# PCB_SCH_Right_Main.net
KiCad netlist of a schematic drawn in EasyEDA Pro
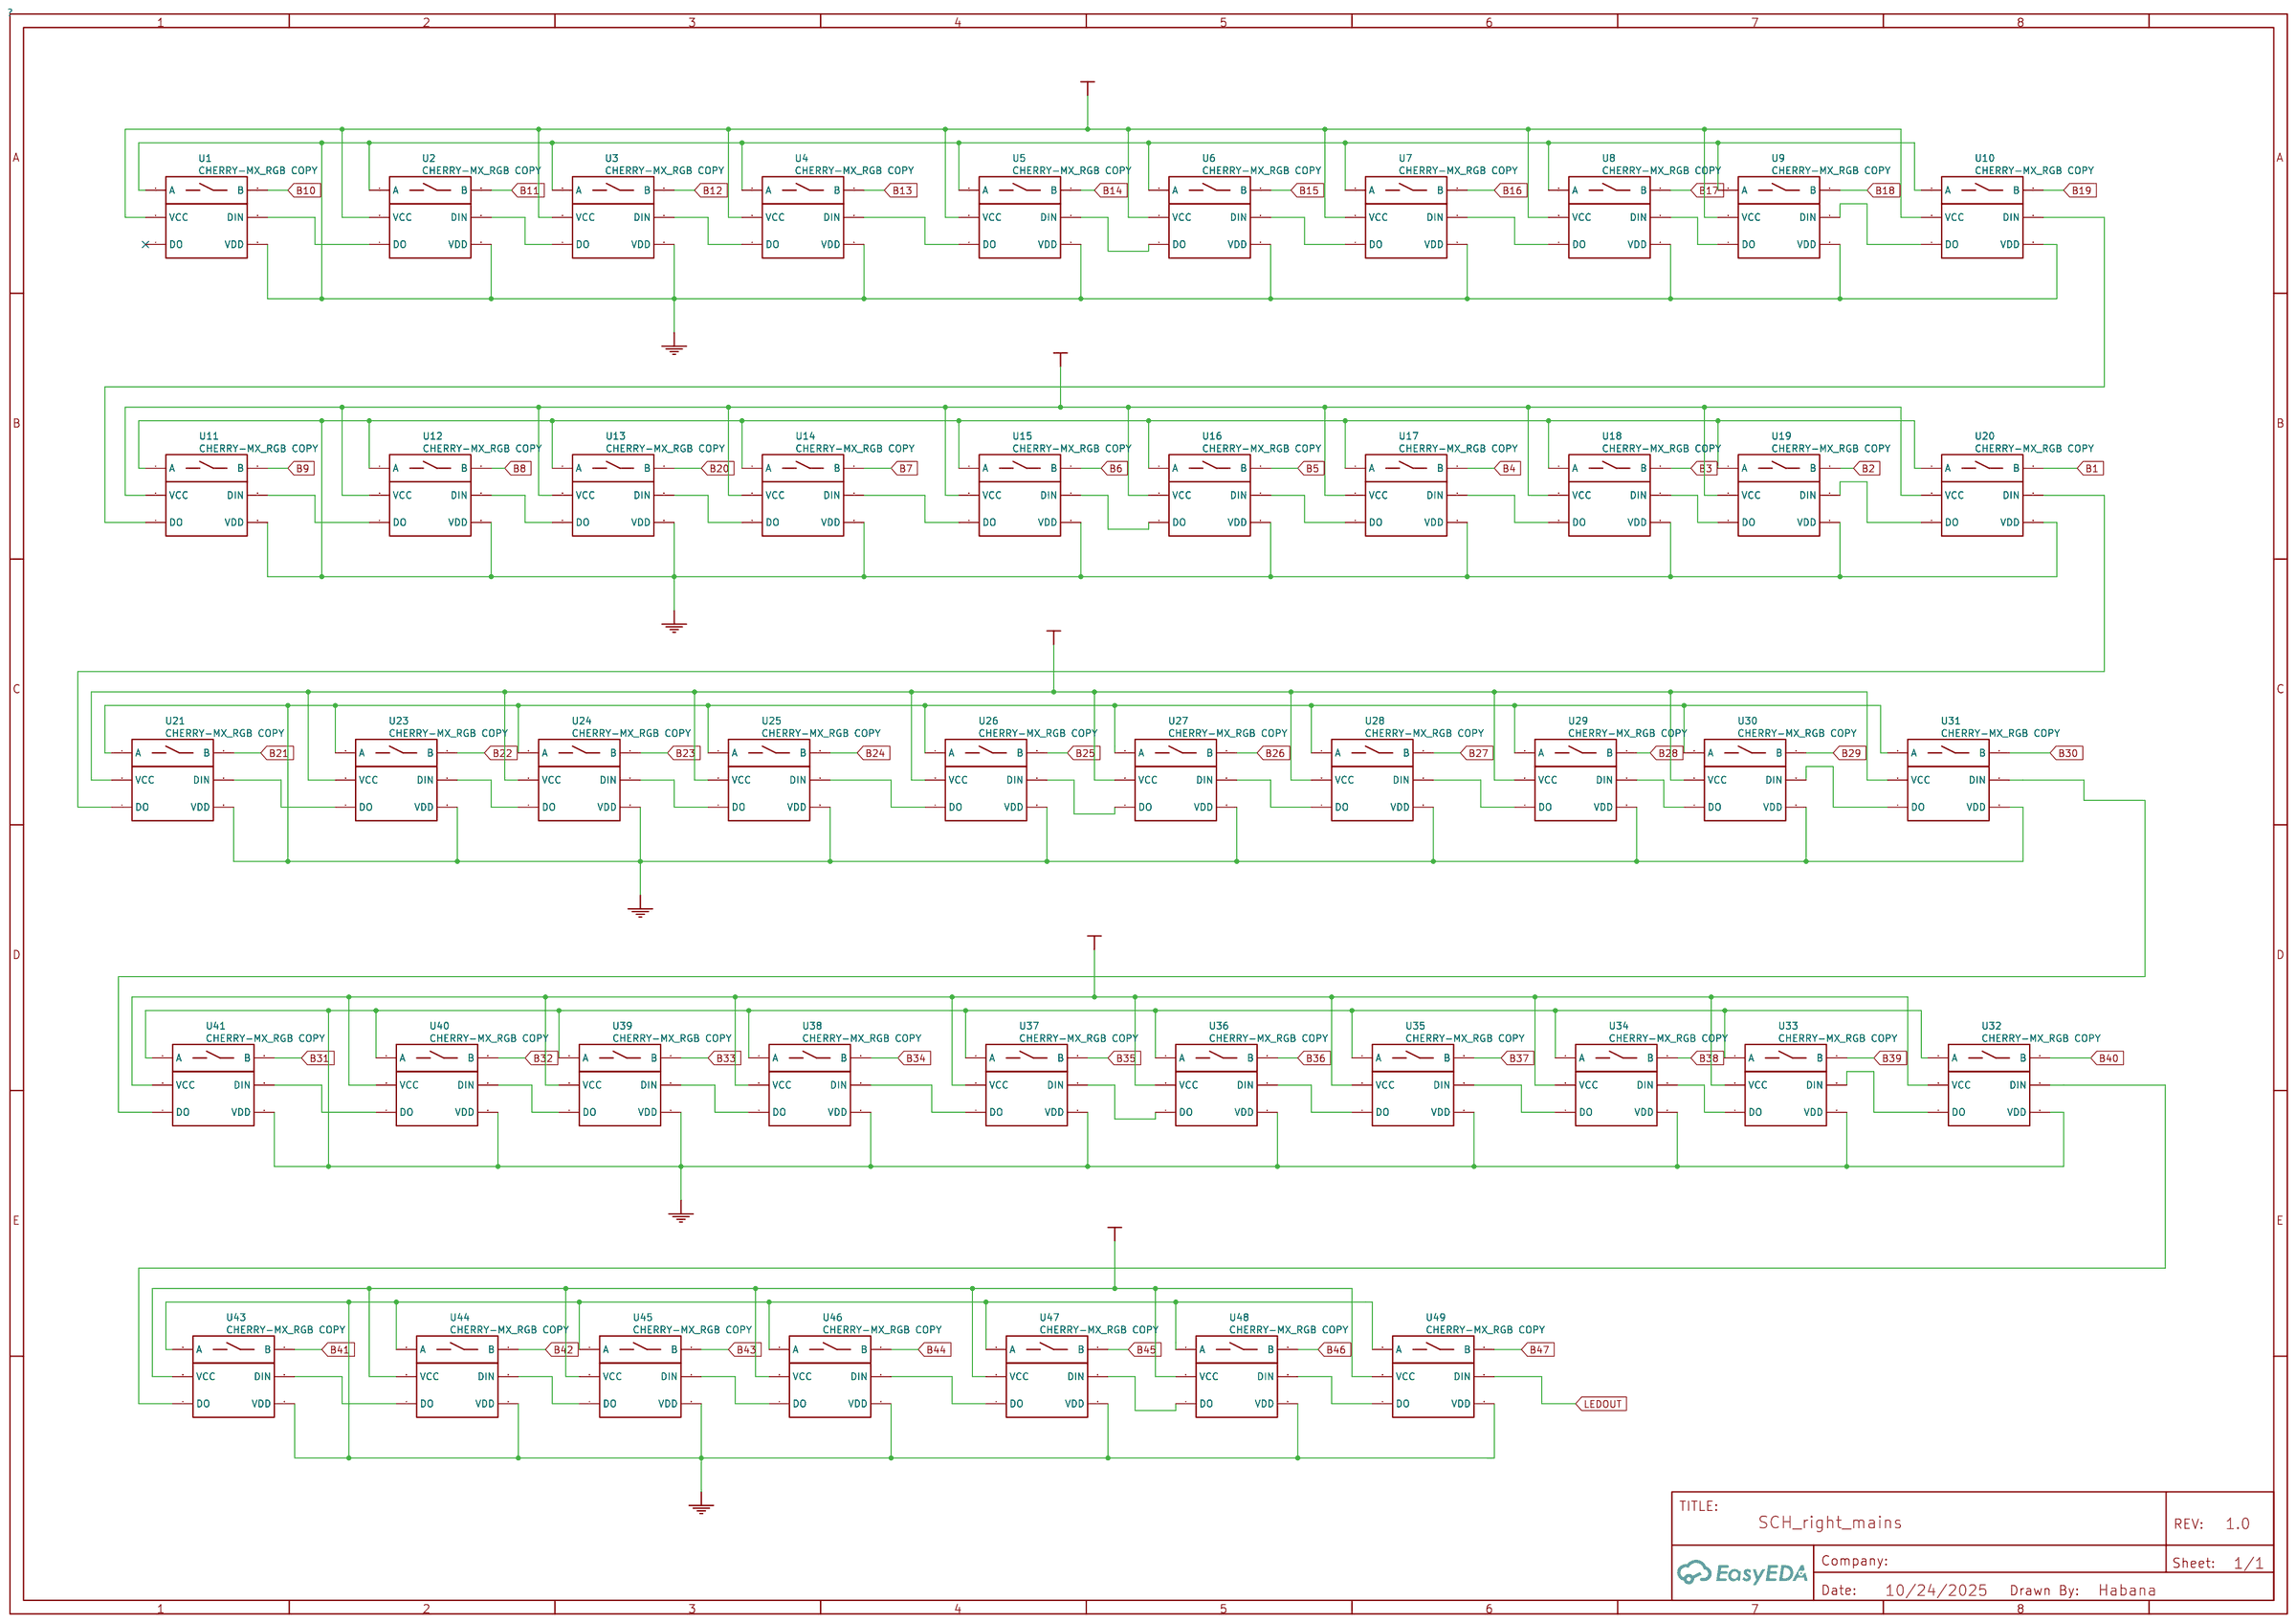
[diagram p0: led and buttons]
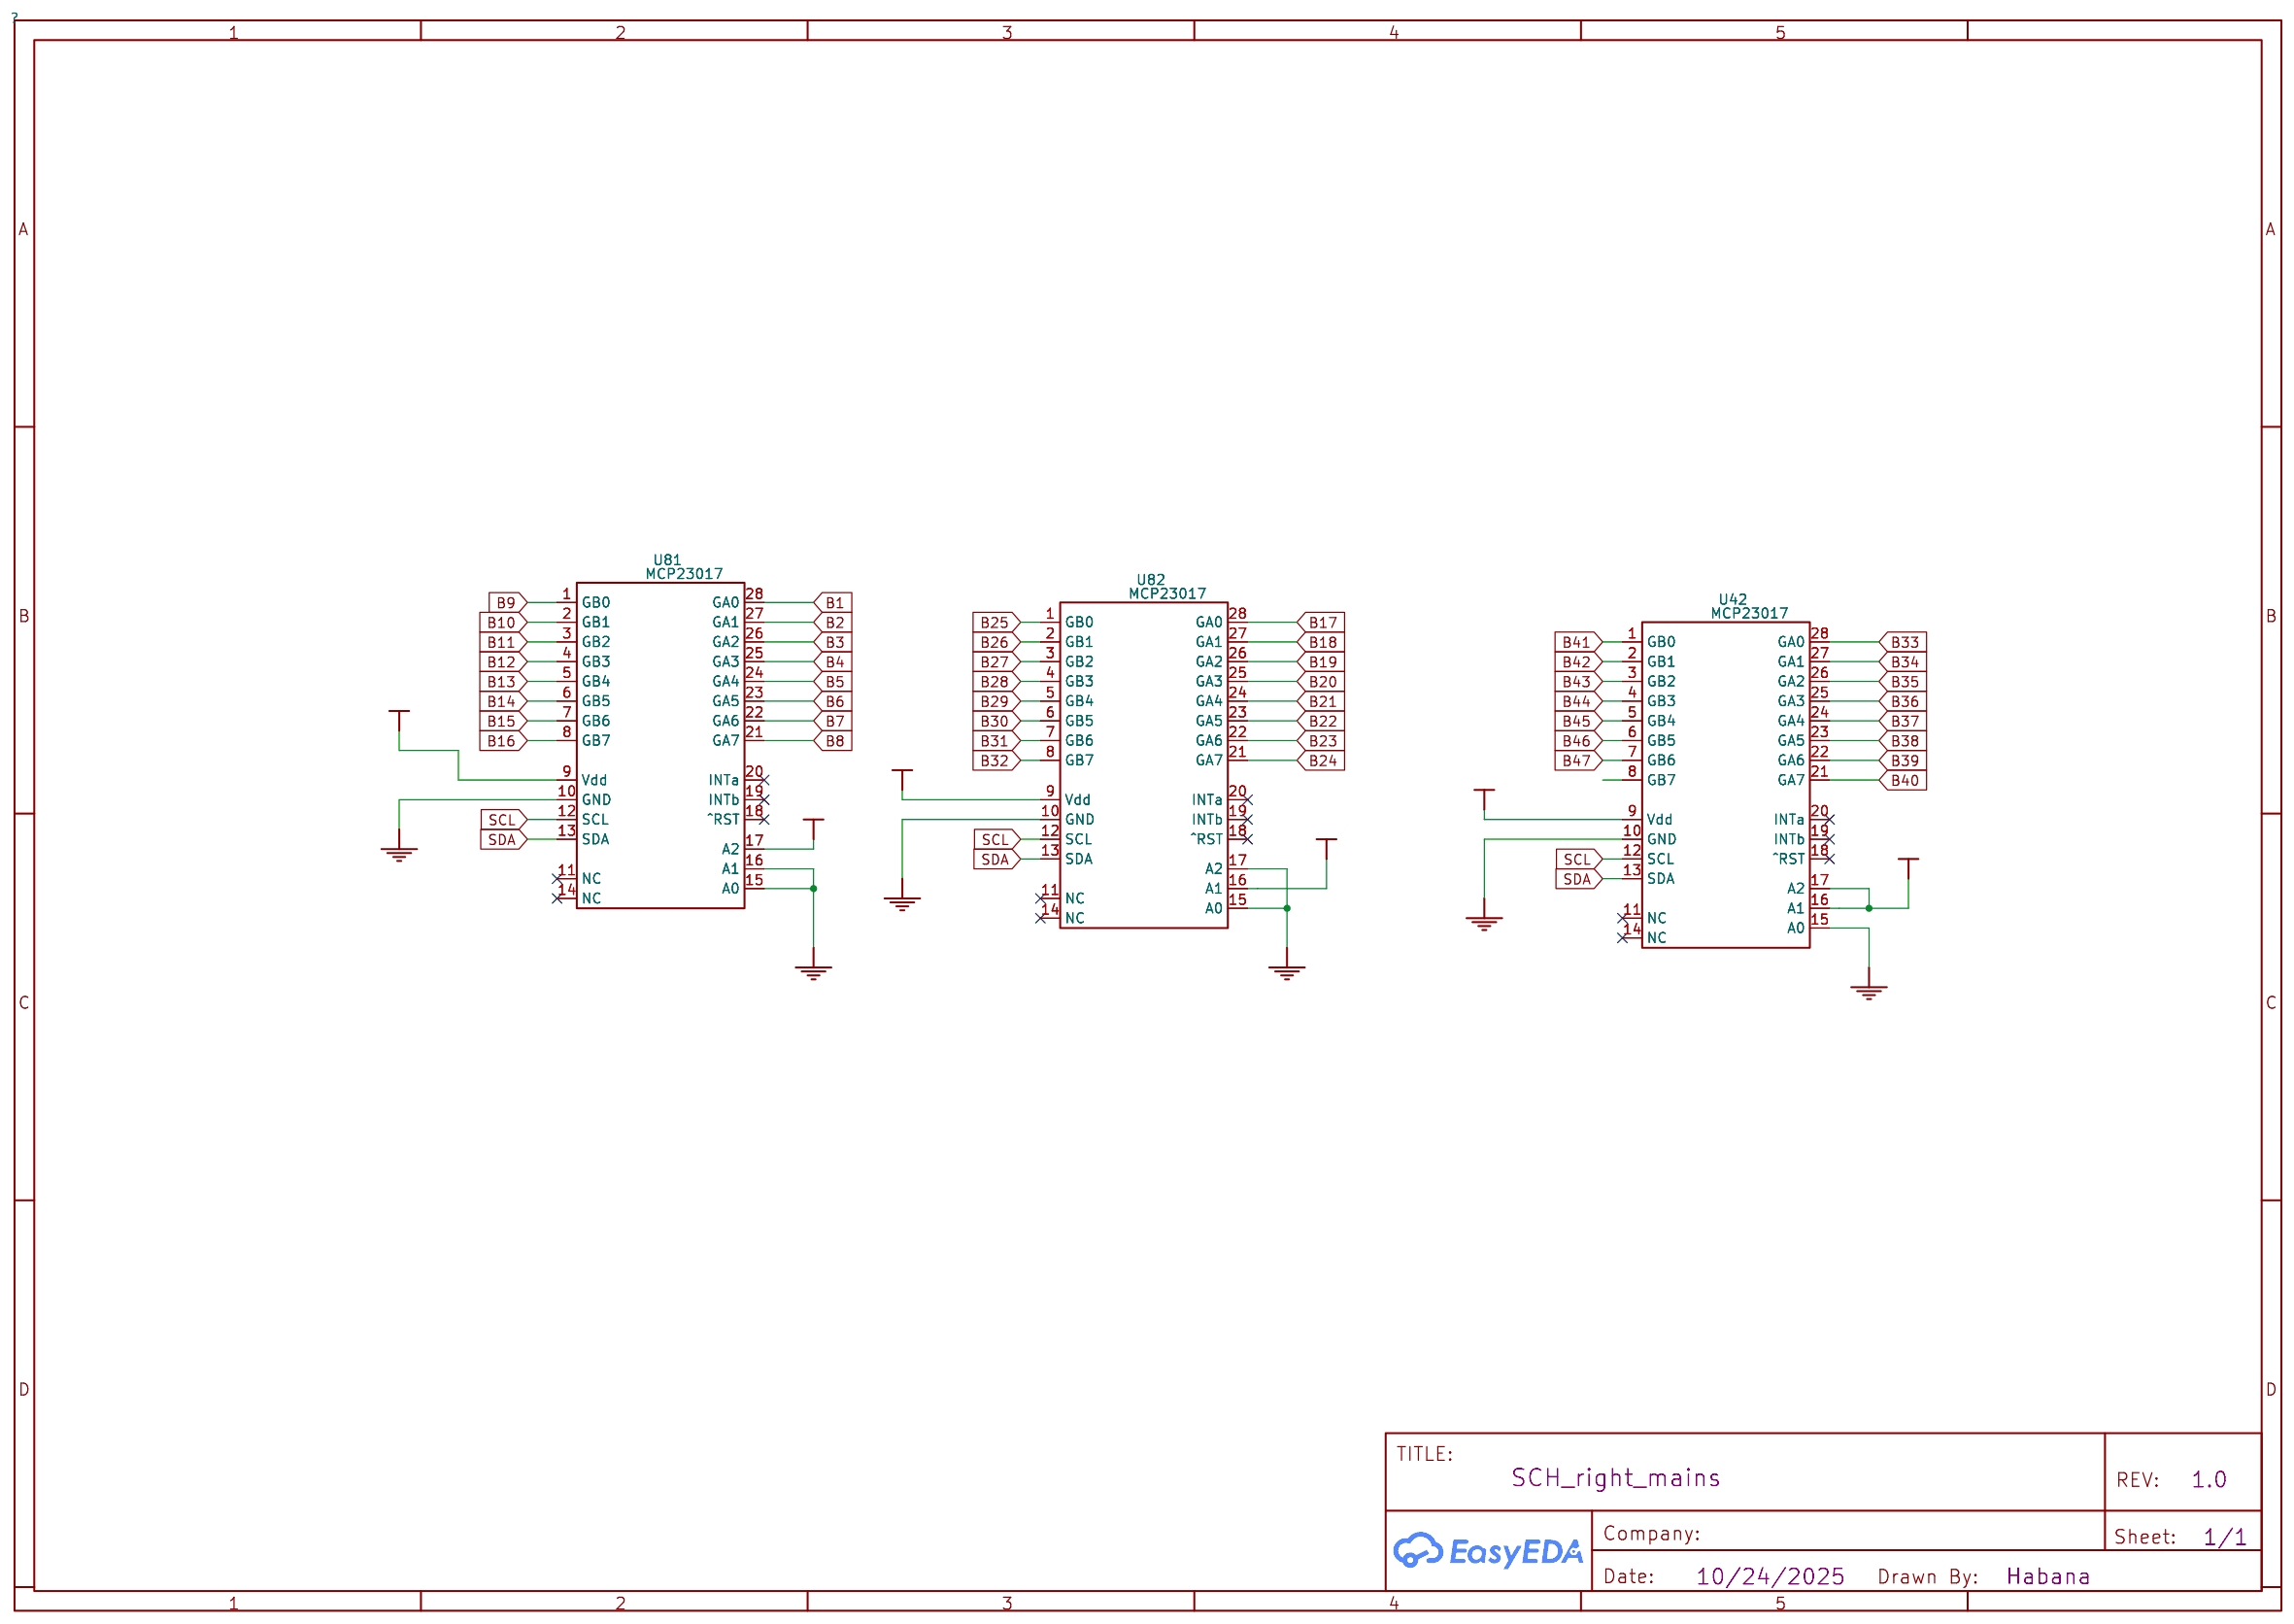
[diagram p1: drivers]
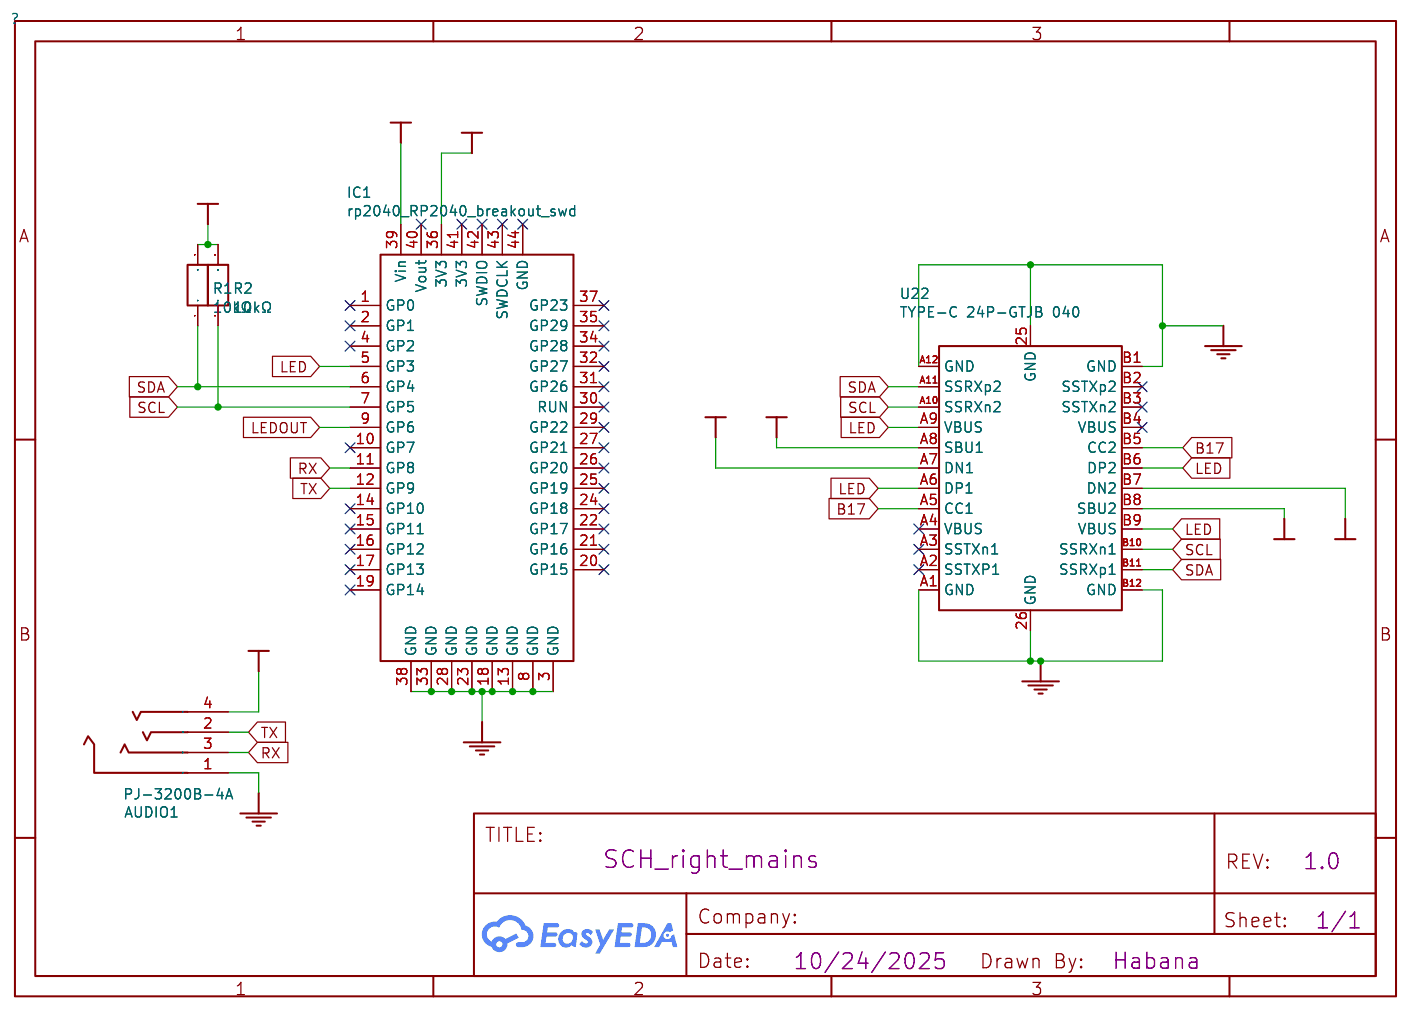
[diagram p2: micro_controller]

(export (version "E")
  (design (tool "Eeschema 10.0.6"))
  (components
    (comp (ref "U1")
      (value "CHERRY-MX_RGB COPY")
      (fields (field (name "Contributor") "unrealin01"))
      (libsource (lib "easyedapro") (part "CHERRY-MX_RGB COPY"))
    )
    (comp (ref "U2")
      (value "CHERRY-MX_RGB COPY")
      (fields (field (name "Contributor") "unrealin01"))
      (libsource (lib "easyedapro") (part "CHERRY-MX_RGB COPY"))
    )
    (comp (ref "U3")
      (value "CHERRY-MX_RGB COPY")
      (fields (field (name "Contributor") "unrealin01"))
      (libsource (lib "easyedapro") (part "CHERRY-MX_RGB COPY"))
    )
    (comp (ref "U4")
      (value "CHERRY-MX_RGB COPY")
      (fields (field (name "Contributor") "unrealin01"))
      (libsource (lib "easyedapro") (part "CHERRY-MX_RGB COPY"))
    )
    (comp (ref "U5")
      (value "CHERRY-MX_RGB COPY")
      (fields (field (name "Contributor") "unrealin01"))
      (libsource (lib "easyedapro") (part "CHERRY-MX_RGB COPY"))
    )
    (comp (ref "U6")
      (value "CHERRY-MX_RGB COPY")
      (fields (field (name "Contributor") "unrealin01"))
      (libsource (lib "easyedapro") (part "CHERRY-MX_RGB COPY"))
    )
    (comp (ref "U7")
      (value "CHERRY-MX_RGB COPY")
      (fields (field (name "Contributor") "unrealin01"))
      (libsource (lib "easyedapro") (part "CHERRY-MX_RGB COPY"))
    )
    (comp (ref "U8")
      (value "CHERRY-MX_RGB COPY")
      (fields (field (name "Contributor") "unrealin01"))
      (libsource (lib "easyedapro") (part "CHERRY-MX_RGB COPY"))
    )
    (comp (ref "U9")
      (value "CHERRY-MX_RGB COPY")
      (fields (field (name "Contributor") "unrealin01"))
      (libsource (lib "easyedapro") (part "CHERRY-MX_RGB COPY"))
    )
    (comp (ref "U10")
      (value "CHERRY-MX_RGB COPY")
      (fields (field (name "Contributor") "unrealin01"))
      (libsource (lib "easyedapro") (part "CHERRY-MX_RGB COPY"))
    )
    (comp (ref "U11")
      (value "CHERRY-MX_RGB COPY")
      (fields (field (name "Contributor") "unrealin01"))
      (libsource (lib "easyedapro") (part "CHERRY-MX_RGB COPY"))
    )
    (comp (ref "U12")
      (value "CHERRY-MX_RGB COPY")
      (fields (field (name "Contributor") "unrealin01"))
      (libsource (lib "easyedapro") (part "CHERRY-MX_RGB COPY"))
    )
    (comp (ref "U13")
      (value "CHERRY-MX_RGB COPY")
      (fields (field (name "Contributor") "unrealin01"))
      (libsource (lib "easyedapro") (part "CHERRY-MX_RGB COPY"))
    )
    (comp (ref "U14")
      (value "CHERRY-MX_RGB COPY")
      (fields (field (name "Contributor") "unrealin01"))
      (libsource (lib "easyedapro") (part "CHERRY-MX_RGB COPY"))
    )
    (comp (ref "U15")
      (value "CHERRY-MX_RGB COPY")
      (fields (field (name "Contributor") "unrealin01"))
      (libsource (lib "easyedapro") (part "CHERRY-MX_RGB COPY"))
    )
    (comp (ref "U16")
      (value "CHERRY-MX_RGB COPY")
      (fields (field (name "Contributor") "unrealin01"))
      (libsource (lib "easyedapro") (part "CHERRY-MX_RGB COPY"))
    )
    (comp (ref "U17")
      (value "CHERRY-MX_RGB COPY")
      (fields (field (name "Contributor") "unrealin01"))
      (libsource (lib "easyedapro") (part "CHERRY-MX_RGB COPY"))
    )
    (comp (ref "U18")
      (value "CHERRY-MX_RGB COPY")
      (fields (field (name "Contributor") "unrealin01"))
      (libsource (lib "easyedapro") (part "CHERRY-MX_RGB COPY"))
    )
    (comp (ref "U19")
      (value "CHERRY-MX_RGB COPY")
      (fields (field (name "Contributor") "unrealin01"))
      (libsource (lib "easyedapro") (part "CHERRY-MX_RGB COPY"))
    )
    (comp (ref "U20")
      (value "CHERRY-MX_RGB COPY")
      (fields (field (name "Contributor") "unrealin01"))
      (libsource (lib "easyedapro") (part "CHERRY-MX_RGB COPY"))
    )
    (comp (ref "U21")
      (value "CHERRY-MX_RGB COPY")
      (fields (field (name "Contributor") "unrealin01"))
      (libsource (lib "easyedapro") (part "CHERRY-MX_RGB COPY"))
    )
    (comp (ref "U23")
      (value "CHERRY-MX_RGB COPY")
      (fields (field (name "Contributor") "unrealin01"))
      (libsource (lib "easyedapro") (part "CHERRY-MX_RGB COPY"))
    )
    (comp (ref "U24")
      (value "CHERRY-MX_RGB COPY")
      (fields (field (name "Contributor") "unrealin01"))
      (libsource (lib "easyedapro") (part "CHERRY-MX_RGB COPY"))
    )
    (comp (ref "U25")
      (value "CHERRY-MX_RGB COPY")
      (fields (field (name "Contributor") "unrealin01"))
      (libsource (lib "easyedapro") (part "CHERRY-MX_RGB COPY"))
    )
    (comp (ref "U26")
      (value "CHERRY-MX_RGB COPY")
      (fields (field (name "Contributor") "unrealin01"))
      (libsource (lib "easyedapro") (part "CHERRY-MX_RGB COPY"))
    )
    (comp (ref "U27")
      (value "CHERRY-MX_RGB COPY")
      (fields (field (name "Contributor") "unrealin01"))
      (libsource (lib "easyedapro") (part "CHERRY-MX_RGB COPY"))
    )
    (comp (ref "U28")
      (value "CHERRY-MX_RGB COPY")
      (fields (field (name "Contributor") "unrealin01"))
      (libsource (lib "easyedapro") (part "CHERRY-MX_RGB COPY"))
    )
    (comp (ref "U29")
      (value "CHERRY-MX_RGB COPY")
      (fields (field (name "Contributor") "unrealin01"))
      (libsource (lib "easyedapro") (part "CHERRY-MX_RGB COPY"))
    )
    (comp (ref "U30")
      (value "CHERRY-MX_RGB COPY")
      (fields (field (name "Contributor") "unrealin01"))
      (libsource (lib "easyedapro") (part "CHERRY-MX_RGB COPY"))
    )
    (comp (ref "U31")
      (value "CHERRY-MX_RGB COPY")
      (fields (field (name "Contributor") "unrealin01"))
      (libsource (lib "easyedapro") (part "CHERRY-MX_RGB COPY"))
    )
    (comp (ref "U32")
      (value "CHERRY-MX_RGB COPY")
      (fields (field (name "Contributor") "unrealin01"))
      (libsource (lib "easyedapro") (part "CHERRY-MX_RGB COPY"))
    )
    (comp (ref "U33")
      (value "CHERRY-MX_RGB COPY")
      (fields (field (name "Contributor") "unrealin01"))
      (libsource (lib "easyedapro") (part "CHERRY-MX_RGB COPY"))
    )
    (comp (ref "U34")
      (value "CHERRY-MX_RGB COPY")
      (fields (field (name "Contributor") "unrealin01"))
      (libsource (lib "easyedapro") (part "CHERRY-MX_RGB COPY"))
    )
    (comp (ref "U35")
      (value "CHERRY-MX_RGB COPY")
      (fields (field (name "Contributor") "unrealin01"))
      (libsource (lib "easyedapro") (part "CHERRY-MX_RGB COPY"))
    )
    (comp (ref "U36")
      (value "CHERRY-MX_RGB COPY")
      (fields (field (name "Contributor") "unrealin01"))
      (libsource (lib "easyedapro") (part "CHERRY-MX_RGB COPY"))
    )
    (comp (ref "U37")
      (value "CHERRY-MX_RGB COPY")
      (fields (field (name "Contributor") "unrealin01"))
      (libsource (lib "easyedapro") (part "CHERRY-MX_RGB COPY"))
    )
    (comp (ref "U38")
      (value "CHERRY-MX_RGB COPY")
      (fields (field (name "Contributor") "unrealin01"))
      (libsource (lib "easyedapro") (part "CHERRY-MX_RGB COPY"))
    )
    (comp (ref "U39")
      (value "CHERRY-MX_RGB COPY")
      (fields (field (name "Contributor") "unrealin01"))
      (libsource (lib "easyedapro") (part "CHERRY-MX_RGB COPY"))
    )
    (comp (ref "U40")
      (value "CHERRY-MX_RGB COPY")
      (fields (field (name "Contributor") "unrealin01"))
      (libsource (lib "easyedapro") (part "CHERRY-MX_RGB COPY"))
    )
    (comp (ref "U41")
      (value "CHERRY-MX_RGB COPY")
      (fields (field (name "Contributor") "unrealin01"))
      (libsource (lib "easyedapro") (part "CHERRY-MX_RGB COPY"))
    )
    (comp (ref "U43")
      (value "CHERRY-MX_RGB COPY")
      (fields (field (name "Contributor") "unrealin01"))
      (libsource (lib "easyedapro") (part "CHERRY-MX_RGB COPY"))
    )
    (comp (ref "U44")
      (value "CHERRY-MX_RGB COPY")
      (fields (field (name "Contributor") "unrealin01"))
      (libsource (lib "easyedapro") (part "CHERRY-MX_RGB COPY"))
    )
    (comp (ref "U45")
      (value "CHERRY-MX_RGB COPY")
      (fields (field (name "Contributor") "unrealin01"))
      (libsource (lib "easyedapro") (part "CHERRY-MX_RGB COPY"))
    )
    (comp (ref "U46")
      (value "CHERRY-MX_RGB COPY")
      (fields (field (name "Contributor") "unrealin01"))
      (libsource (lib "easyedapro") (part "CHERRY-MX_RGB COPY"))
    )
    (comp (ref "U47")
      (value "CHERRY-MX_RGB COPY")
      (fields (field (name "Contributor") "unrealin01"))
      (libsource (lib "easyedapro") (part "CHERRY-MX_RGB COPY"))
    )
    (comp (ref "U48")
      (value "CHERRY-MX_RGB COPY")
      (fields (field (name "Contributor") "unrealin01"))
      (libsource (lib "easyedapro") (part "CHERRY-MX_RGB COPY"))
    )
    (comp (ref "U49")
      (value "CHERRY-MX_RGB COPY")
      (fields (field (name "Contributor") "unrealin01"))
      (libsource (lib "easyedapro") (part "CHERRY-MX_RGB COPY"))
    )
    (comp (ref "U42")
      (value "MCP23017")
      (fields (field (name "Contributor") "tsvstar"))
      (libsource (lib "easyedapro") (part "MCP23017"))
    )
    (comp (ref "U81")
      (value "MCP23017")
      (fields (field (name "Contributor") "tsvstar"))
      (libsource (lib "easyedapro") (part "MCP23017"))
    )
    (comp (ref "U82")
      (value "MCP23017")
      (fields (field (name "Contributor") "tsvstar"))
      (libsource (lib "easyedapro") (part "MCP23017"))
    )
    (comp (ref "AUDIO1")
      (value "PJ-3200B-4A")
      (footprint "easyedapro:AUDIO-TH_PJ-3200B-4A")
      (fields (field (name "Manufacturer") "韩国韩荣") (field (name "Contributor") "LCSC"))
      (libsource (lib "easyedapro") (part "PJ-3200B-4A"))
    )
    (comp (ref "IC1")
      (value "rp2040_RP2040_breakout_swd")
      (fields (field (name "Contributor") "rataweb"))
      (libsource (lib "easyedapro") (part "rp2040_RP2040_breakout_swd"))
    )
    (comp (ref "R1")
      (value "10kΩ")
      (footprint "easyedapro:R1206")
      (fields
        (field (name "Manufacturer Part") "RCT0610KJLF")
        (field (name "Manufacturer") "HKR(香港电阻)")
        (field (name "Contributor") "LCSC")
      )
      (libsource (lib "easyedapro") (part "10kΩ"))
    )
    (comp (ref "R2")
      (value "10kΩ")
      (footprint "easyedapro:R1206")
      (fields
        (field (name "Manufacturer Part") "RCT0610KJLF")
        (field (name "Manufacturer") "HKR(香港电阻)")
        (field (name "Contributor") "LCSC")
      )
      (libsource (lib "easyedapro") (part "10kΩ"))
    )
    (comp (ref "U22")
      (value "TYPE-C 24P-GTJB 040")
      (footprint "easyedapro:USB-C-SMD_TYPE-C-24P-GTJB-040")
      (fields (field (name "Manufacturer") "SHOU HAN(首韩)") (field (name "Contributor") "lcsc"))
      (libsource (lib "easyedapro") (part "TYPE-C 24P-GTJB 040"))
    )
  )
  (nets
    (net (code "1") (name "+5V") (class "Default")
      (node (ref "IC1") (pin "36") (pinfunction "3V3_36") (pintype "unspecified"))
      (node (ref "R1") (pin "2") (pinfunction "2_2") (pintype "unspecified"))
      (node (ref "R2") (pin "2") (pinfunction "2_2") (pintype "unspecified"))
      (node (ref "U1") (pin "3") (pinfunction "VCC_3") (pintype "unspecified"))
      (node (ref "U10") (pin "3") (pinfunction "VCC_3") (pintype "unspecified"))
      (node (ref "U11") (pin "3") (pinfunction "VCC_3") (pintype "unspecified"))
      (node (ref "U12") (pin "3") (pinfunction "VCC_3") (pintype "unspecified"))
      (node (ref "U13") (pin "3") (pinfunction "VCC_3") (pintype "unspecified"))
      (node (ref "U14") (pin "3") (pinfunction "VCC_3") (pintype "unspecified"))
      (node (ref "U15") (pin "3") (pinfunction "VCC_3") (pintype "unspecified"))
      (node (ref "U16") (pin "3") (pinfunction "VCC_3") (pintype "unspecified"))
      (node (ref "U17") (pin "3") (pinfunction "VCC_3") (pintype "unspecified"))
      (node (ref "U18") (pin "3") (pinfunction "VCC_3") (pintype "unspecified"))
      (node (ref "U19") (pin "3") (pinfunction "VCC_3") (pintype "unspecified"))
      (node (ref "U2") (pin "3") (pinfunction "VCC_3") (pintype "unspecified"))
      (node (ref "U20") (pin "3") (pinfunction "VCC_3") (pintype "unspecified"))
      (node (ref "U21") (pin "3") (pinfunction "VCC_3") (pintype "unspecified"))
      (node (ref "U22") (pin "A8") (pinfunction "SBU1_A8") (pintype "unspecified"))
      (node (ref "U22") (pin "B8") (pinfunction "SBU2_B8") (pintype "unspecified"))
      (node (ref "U23") (pin "3") (pinfunction "VCC_3") (pintype "unspecified"))
      (node (ref "U24") (pin "3") (pinfunction "VCC_3") (pintype "unspecified"))
      (node (ref "U25") (pin "3") (pinfunction "VCC_3") (pintype "unspecified"))
      (node (ref "U26") (pin "3") (pinfunction "VCC_3") (pintype "unspecified"))
      (node (ref "U27") (pin "3") (pinfunction "VCC_3") (pintype "unspecified"))
      (node (ref "U28") (pin "3") (pinfunction "VCC_3") (pintype "unspecified"))
      (node (ref "U29") (pin "3") (pinfunction "VCC_3") (pintype "unspecified"))
      (node (ref "U3") (pin "3") (pinfunction "VCC_3") (pintype "unspecified"))
      (node (ref "U30") (pin "3") (pinfunction "VCC_3") (pintype "unspecified"))
      (node (ref "U31") (pin "3") (pinfunction "VCC_3") (pintype "unspecified"))
      (node (ref "U32") (pin "3") (pinfunction "VCC_3") (pintype "unspecified"))
      (node (ref "U33") (pin "3") (pinfunction "VCC_3") (pintype "unspecified"))
      (node (ref "U34") (pin "3") (pinfunction "VCC_3") (pintype "unspecified"))
      (node (ref "U35") (pin "3") (pinfunction "VCC_3") (pintype "unspecified"))
      (node (ref "U36") (pin "3") (pinfunction "VCC_3") (pintype "unspecified"))
      (node (ref "U37") (pin "3") (pinfunction "VCC_3") (pintype "unspecified"))
      (node (ref "U38") (pin "3") (pinfunction "VCC_3") (pintype "unspecified"))
      (node (ref "U39") (pin "3") (pinfunction "VCC_3") (pintype "unspecified"))
      (node (ref "U4") (pin "3") (pinfunction "VCC_3") (pintype "unspecified"))
      (node (ref "U40") (pin "3") (pinfunction "VCC_3") (pintype "unspecified"))
      (node (ref "U41") (pin "3") (pinfunction "VCC_3") (pintype "unspecified"))
      (node (ref "U43") (pin "3") (pinfunction "VCC_3") (pintype "unspecified"))
      (node (ref "U44") (pin "3") (pinfunction "VCC_3") (pintype "unspecified"))
      (node (ref "U45") (pin "3") (pinfunction "VCC_3") (pintype "unspecified"))
      (node (ref "U46") (pin "3") (pinfunction "VCC_3") (pintype "unspecified"))
      (node (ref "U47") (pin "3") (pinfunction "VCC_3") (pintype "unspecified"))
      (node (ref "U48") (pin "3") (pinfunction "VCC_3") (pintype "unspecified"))
      (node (ref "U49") (pin "3") (pinfunction "VCC_3") (pintype "unspecified"))
      (node (ref "U5") (pin "3") (pinfunction "VCC_3") (pintype "unspecified"))
      (node (ref "U6") (pin "3") (pinfunction "VCC_3") (pintype "unspecified"))
      (node (ref "U7") (pin "3") (pinfunction "VCC_3") (pintype "unspecified"))
      (node (ref "U8") (pin "3") (pinfunction "VCC_3") (pintype "unspecified"))
      (node (ref "U9") (pin "3") (pinfunction "VCC_3") (pintype "unspecified"))
    )
    (net (code "2") (name "B1") (class "Default")
      (node (ref "U20") (pin "2") (pinfunction "B_2") (pintype "unspecified"))
      (node (ref "U81") (pin "28") (pinfunction "GA0_28") (pintype "unspecified"))
    )
    (net (code "3") (name "B2") (class "Default")
      (node (ref "U19") (pin "2") (pinfunction "B_2") (pintype "unspecified"))
      (node (ref "U81") (pin "27") (pinfunction "GA1_27") (pintype "unspecified"))
    )
    (net (code "4") (name "B3") (class "Default")
      (node (ref "U18") (pin "2") (pinfunction "B_2") (pintype "unspecified"))
      (node (ref "U81") (pin "26") (pinfunction "GA2_26") (pintype "unspecified"))
    )
    (net (code "5") (name "B4") (class "Default")
      (node (ref "U17") (pin "2") (pinfunction "B_2") (pintype "unspecified"))
      (node (ref "U81") (pin "25") (pinfunction "GA3_25") (pintype "unspecified"))
    )
    (net (code "6") (name "B5") (class "Default")
      (node (ref "U16") (pin "2") (pinfunction "B_2") (pintype "unspecified"))
      (node (ref "U81") (pin "24") (pinfunction "GA4_24") (pintype "unspecified"))
    )
    (net (code "7") (name "B6") (class "Default")
      (node (ref "U15") (pin "2") (pinfunction "B_2") (pintype "unspecified"))
      (node (ref "U81") (pin "23") (pinfunction "GA5_23") (pintype "unspecified"))
    )
    (net (code "8") (name "B7") (class "Default")
      (node (ref "U14") (pin "2") (pinfunction "B_2") (pintype "unspecified"))
      (node (ref "U81") (pin "22") (pinfunction "GA6_22") (pintype "unspecified"))
    )
    (net (code "9") (name "B8") (class "Default")
      (node (ref "U12") (pin "2") (pinfunction "B_2") (pintype "unspecified"))
      (node (ref "U81") (pin "21") (pinfunction "GA7_21") (pintype "unspecified"))
    )
    (net (code "10") (name "B9") (class "Default")
      (node (ref "U11") (pin "2") (pinfunction "B_2") (pintype "unspecified"))
      (node (ref "U81") (pin "1") (pinfunction "GB0_1") (pintype "unspecified"))
    )
    (net (code "11") (name "B10") (class "Default")
      (node (ref "U1") (pin "2") (pinfunction "B_2") (pintype "unspecified"))
      (node (ref "U81") (pin "2") (pinfunction "GB1_2") (pintype "unspecified"))
    )
    (net (code "12") (name "B11") (class "Default")
      (node (ref "U2") (pin "2") (pinfunction "B_2") (pintype "unspecified"))
      (node (ref "U81") (pin "3") (pinfunction "GB2_3") (pintype "unspecified"))
    )
    (net (code "13") (name "B12") (class "Default")
      (node (ref "U3") (pin "2") (pinfunction "B_2") (pintype "unspecified"))
      (node (ref "U81") (pin "4") (pinfunction "GB3_4") (pintype "unspecified"))
    )
    (net (code "14") (name "B13") (class "Default")
      (node (ref "U4") (pin "2") (pinfunction "B_2") (pintype "unspecified"))
      (node (ref "U81") (pin "5") (pinfunction "GB4_5") (pintype "unspecified"))
    )
    (net (code "15") (name "B14") (class "Default")
      (node (ref "U5") (pin "2") (pinfunction "B_2") (pintype "unspecified"))
      (node (ref "U81") (pin "6") (pinfunction "GB5_6") (pintype "unspecified"))
    )
    (net (code "16") (name "B15") (class "Default")
      (node (ref "U6") (pin "2") (pinfunction "B_2") (pintype "unspecified"))
      (node (ref "U81") (pin "7") (pinfunction "GB6_7") (pintype "unspecified"))
    )
    (net (code "17") (name "B16") (class "Default")
      (node (ref "U7") (pin "2") (pinfunction "B_2") (pintype "unspecified"))
      (node (ref "U81") (pin "8") (pinfunction "GB7_8") (pintype "unspecified"))
    )
    (net (code "18") (name "B17") (class "Default")
      (node (ref "U22") (pin "A5") (pinfunction "CC1_A5") (pintype "unspecified"))
      (node (ref "U22") (pin "B5") (pinfunction "CC2_B5") (pintype "unspecified"))
      (node (ref "U8") (pin "2") (pinfunction "B_2") (pintype "unspecified"))
      (node (ref "U82") (pin "28") (pinfunction "GA0_28") (pintype "unspecified"))
    )
    (net (code "19") (name "B18") (class "Default")
      (node (ref "U82") (pin "27") (pinfunction "GA1_27") (pintype "unspecified"))
      (node (ref "U9") (pin "2") (pinfunction "B_2") (pintype "unspecified"))
    )
    (net (code "20") (name "B19") (class "Default")
      (node (ref "U10") (pin "2") (pinfunction "B_2") (pintype "unspecified"))
      (node (ref "U82") (pin "26") (pinfunction "GA2_26") (pintype "unspecified"))
    )
    (net (code "21") (name "B20") (class "Default")
      (node (ref "U13") (pin "2") (pinfunction "B_2") (pintype "unspecified"))
      (node (ref "U82") (pin "25") (pinfunction "GA3_25") (pintype "unspecified"))
    )
    (net (code "22") (name "B21") (class "Default")
      (node (ref "U21") (pin "2") (pinfunction "B_2") (pintype "unspecified"))
      (node (ref "U82") (pin "24") (pinfunction "GA4_24") (pintype "unspecified"))
    )
    (net (code "23") (name "B22") (class "Default")
      (node (ref "U23") (pin "2") (pinfunction "B_2") (pintype "unspecified"))
      (node (ref "U82") (pin "23") (pinfunction "GA5_23") (pintype "unspecified"))
    )
    (net (code "24") (name "B23") (class "Default")
      (node (ref "U24") (pin "2") (pinfunction "B_2") (pintype "unspecified"))
      (node (ref "U82") (pin "22") (pinfunction "GA6_22") (pintype "unspecified"))
    )
    (net (code "25") (name "B24") (class "Default")
      (node (ref "U25") (pin "2") (pinfunction "B_2") (pintype "unspecified"))
      (node (ref "U82") (pin "21") (pinfunction "GA7_21") (pintype "unspecified"))
    )
    (net (code "26") (name "B25") (class "Default")
      (node (ref "U26") (pin "2") (pinfunction "B_2") (pintype "unspecified"))
      (node (ref "U82") (pin "1") (pinfunction "GB0_1") (pintype "unspecified"))
    )
    (net (code "27") (name "B26") (class "Default")
      (node (ref "U27") (pin "2") (pinfunction "B_2") (pintype "unspecified"))
      (node (ref "U82") (pin "2") (pinfunction "GB1_2") (pintype "unspecified"))
    )
    (net (code "28") (name "B27") (class "Default")
      (node (ref "U28") (pin "2") (pinfunction "B_2") (pintype "unspecified"))
      (node (ref "U82") (pin "3") (pinfunction "GB2_3") (pintype "unspecified"))
    )
    (net (code "29") (name "B28") (class "Default")
      (node (ref "U29") (pin "2") (pinfunction "B_2") (pintype "unspecified"))
      (node (ref "U82") (pin "4") (pinfunction "GB3_4") (pintype "unspecified"))
    )
    (net (code "30") (name "B29") (class "Default")
      (node (ref "U30") (pin "2") (pinfunction "B_2") (pintype "unspecified"))
      (node (ref "U82") (pin "5") (pinfunction "GB4_5") (pintype "unspecified"))
    )
    (net (code "31") (name "B30") (class "Default")
      (node (ref "U31") (pin "2") (pinfunction "B_2") (pintype "unspecified"))
      (node (ref "U82") (pin "6") (pinfunction "GB5_6") (pintype "unspecified"))
    )
    (net (code "32") (name "B31") (class "Default")
      (node (ref "U41") (pin "2") (pinfunction "B_2") (pintype "unspecified"))
      (node (ref "U82") (pin "7") (pinfunction "GB6_7") (pintype "unspecified"))
    )
    (net (code "33") (name "B32") (class "Default")
      (node (ref "U40") (pin "2") (pinfunction "B_2") (pintype "unspecified"))
      (node (ref "U82") (pin "8") (pinfunction "GB7_8") (pintype "unspecified"))
    )
    (net (code "34") (name "B33") (class "Default")
      (node (ref "U39") (pin "2") (pinfunction "B_2") (pintype "unspecified"))
      (node (ref "U42") (pin "28") (pinfunction "GA0_28") (pintype "unspecified"))
    )
    (net (code "35") (name "B34") (class "Default")
      (node (ref "U38") (pin "2") (pinfunction "B_2") (pintype "unspecified"))
      (node (ref "U42") (pin "27") (pinfunction "GA1_27") (pintype "unspecified"))
    )
    (net (code "36") (name "B35") (class "Default")
      (node (ref "U37") (pin "2") (pinfunction "B_2") (pintype "unspecified"))
      (node (ref "U42") (pin "26") (pinfunction "GA2_26") (pintype "unspecified"))
    )
    (net (code "37") (name "B36") (class "Default")
      (node (ref "U36") (pin "2") (pinfunction "B_2") (pintype "unspecified"))
      (node (ref "U42") (pin "25") (pinfunction "GA3_25") (pintype "unspecified"))
    )
    (net (code "38") (name "B37") (class "Default")
      (node (ref "U35") (pin "2") (pinfunction "B_2") (pintype "unspecified"))
      (node (ref "U42") (pin "24") (pinfunction "GA4_24") (pintype "unspecified"))
    )
    (net (code "39") (name "B38") (class "Default")
      (node (ref "U34") (pin "2") (pinfunction "B_2") (pintype "unspecified"))
      (node (ref "U42") (pin "23") (pinfunction "GA5_23") (pintype "unspecified"))
    )
    (net (code "40") (name "B39") (class "Default")
      (node (ref "U33") (pin "2") (pinfunction "B_2") (pintype "unspecified"))
      (node (ref "U42") (pin "22") (pinfunction "GA6_22") (pintype "unspecified"))
    )
    (net (code "41") (name "B40") (class "Default")
      (node (ref "U32") (pin "2") (pinfunction "B_2") (pintype "unspecified"))
      (node (ref "U42") (pin "21") (pinfunction "GA7_21") (pintype "unspecified"))
    )
    (net (code "42") (name "B41") (class "Default")
      (node (ref "U42") (pin "1") (pinfunction "GB0_1") (pintype "unspecified"))
      (node (ref "U43") (pin "2") (pinfunction "B_2") (pintype "unspecified"))
    )
    (net (code "43") (name "B42") (class "Default")
      (node (ref "U42") (pin "2") (pinfunction "GB1_2") (pintype "unspecified"))
      (node (ref "U44") (pin "2") (pinfunction "B_2") (pintype "unspecified"))
    )
    (net (code "44") (name "B43") (class "Default")
      (node (ref "U42") (pin "3") (pinfunction "GB2_3") (pintype "unspecified"))
      (node (ref "U45") (pin "2") (pinfunction "B_2") (pintype "unspecified"))
    )
    (net (code "45") (name "B44") (class "Default")
      (node (ref "U42") (pin "4") (pinfunction "GB3_4") (pintype "unspecified"))
      (node (ref "U46") (pin "2") (pinfunction "B_2") (pintype "unspecified"))
    )
    (net (code "46") (name "B45") (class "Default")
      (node (ref "U42") (pin "5") (pinfunction "GB4_5") (pintype "unspecified"))
      (node (ref "U47") (pin "2") (pinfunction "B_2") (pintype "unspecified"))
    )
    (net (code "47") (name "B46") (class "Default")
      (node (ref "U42") (pin "6") (pinfunction "GB5_6") (pintype "unspecified"))
      (node (ref "U48") (pin "2") (pinfunction "B_2") (pintype "unspecified"))
    )
    (net (code "48") (name "B47") (class "Default")
      (node (ref "U42") (pin "7") (pinfunction "GB6_7") (pintype "unspecified"))
      (node (ref "U49") (pin "2") (pinfunction "B_2") (pintype "unspecified"))
    )
    (net (code "49") (name "GND") (class "Default")
      (node (ref "AUDIO1") (pin "1") (pinfunction "1_1") (pintype "unspecified"))
      (node (ref "IC1") (pin "13") (pinfunction "GND_13") (pintype "unspecified"))
      (node (ref "IC1") (pin "18") (pinfunction "GND_18") (pintype "unspecified"))
      (node (ref "IC1") (pin "23") (pinfunction "GND_23") (pintype "unspecified"))
      (node (ref "IC1") (pin "28") (pinfunction "GND_28") (pintype "unspecified"))
      (node (ref "IC1") (pin "3") (pinfunction "GND_3") (pintype "unspecified"))
      (node (ref "IC1") (pin "33") (pinfunction "GND_33") (pintype "unspecified"))
      (node (ref "IC1") (pin "38") (pinfunction "GND_38") (pintype "unspecified"))
      (node (ref "IC1") (pin "8") (pinfunction "GND_8") (pintype "unspecified"))
      (node (ref "U1") (pin "1") (pinfunction "A_1") (pintype "unspecified"))
      (node (ref "U1") (pin "5") (pinfunction "VDD_5") (pintype "unspecified"))
      (node (ref "U10") (pin "1") (pinfunction "A_1") (pintype "unspecified"))
      (node (ref "U10") (pin "5") (pinfunction "VDD_5") (pintype "unspecified"))
      (node (ref "U11") (pin "1") (pinfunction "A_1") (pintype "unspecified"))
      (node (ref "U11") (pin "5") (pinfunction "VDD_5") (pintype "unspecified"))
      (node (ref "U12") (pin "1") (pinfunction "A_1") (pintype "unspecified"))
      (node (ref "U12") (pin "5") (pinfunction "VDD_5") (pintype "unspecified"))
      (node (ref "U13") (pin "1") (pinfunction "A_1") (pintype "unspecified"))
      (node (ref "U13") (pin "5") (pinfunction "VDD_5") (pintype "unspecified"))
      (node (ref "U14") (pin "1") (pinfunction "A_1") (pintype "unspecified"))
      (node (ref "U14") (pin "5") (pinfunction "VDD_5") (pintype "unspecified"))
      (node (ref "U15") (pin "1") (pinfunction "A_1") (pintype "unspecified"))
      (node (ref "U15") (pin "5") (pinfunction "VDD_5") (pintype "unspecified"))
      (node (ref "U16") (pin "1") (pinfunction "A_1") (pintype "unspecified"))
      (node (ref "U16") (pin "5") (pinfunction "VDD_5") (pintype "unspecified"))
      (node (ref "U17") (pin "1") (pinfunction "A_1") (pintype "unspecified"))
      (node (ref "U17") (pin "5") (pinfunction "VDD_5") (pintype "unspecified"))
      (node (ref "U18") (pin "1") (pinfunction "A_1") (pintype "unspecified"))
      (node (ref "U18") (pin "5") (pinfunction "VDD_5") (pintype "unspecified"))
      (node (ref "U19") (pin "1") (pinfunction "A_1") (pintype "unspecified"))
      (node (ref "U19") (pin "5") (pinfunction "VDD_5") (pintype "unspecified"))
      (node (ref "U2") (pin "1") (pinfunction "A_1") (pintype "unspecified"))
      (node (ref "U2") (pin "5") (pinfunction "VDD_5") (pintype "unspecified"))
      (node (ref "U20") (pin "1") (pinfunction "A_1") (pintype "unspecified"))
      (node (ref "U20") (pin "5") (pinfunction "VDD_5") (pintype "unspecified"))
      (node (ref "U21") (pin "1") (pinfunction "A_1") (pintype "unspecified"))
      (node (ref "U21") (pin "5") (pinfunction "VDD_5") (pintype "unspecified"))
      (node (ref "U22") (pin "25") (pinfunction "GND_25") (pintype "unspecified"))
      (node (ref "U22") (pin "26") (pinfunction "GND_26") (pintype "unspecified"))
      (node (ref "U22") (pin "A1") (pinfunction "GND_A1") (pintype "unspecified"))
      (node (ref "U22") (pin "A12") (pinfunction "GND_A12") (pintype "unspecified"))
      (node (ref "U22") (pin "B1") (pinfunction "GND_B1") (pintype "unspecified"))
      (node (ref "U22") (pin "B12") (pinfunction "GND_B12") (pintype "unspecified"))
      (node (ref "U23") (pin "1") (pinfunction "A_1") (pintype "unspecified"))
      (node (ref "U23") (pin "5") (pinfunction "VDD_5") (pintype "unspecified"))
      (node (ref "U24") (pin "1") (pinfunction "A_1") (pintype "unspecified"))
      (node (ref "U24") (pin "5") (pinfunction "VDD_5") (pintype "unspecified"))
      (node (ref "U25") (pin "1") (pinfunction "A_1") (pintype "unspecified"))
      (node (ref "U25") (pin "5") (pinfunction "VDD_5") (pintype "unspecified"))
      (node (ref "U26") (pin "1") (pinfunction "A_1") (pintype "unspecified"))
      (node (ref "U26") (pin "5") (pinfunction "VDD_5") (pintype "unspecified"))
      (node (ref "U27") (pin "1") (pinfunction "A_1") (pintype "unspecified"))
      (node (ref "U27") (pin "5") (pinfunction "VDD_5") (pintype "unspecified"))
      (node (ref "U28") (pin "1") (pinfunction "A_1") (pintype "unspecified"))
      (node (ref "U28") (pin "5") (pinfunction "VDD_5") (pintype "unspecified"))
      (node (ref "U29") (pin "1") (pinfunction "A_1") (pintype "unspecified"))
      (node (ref "U29") (pin "5") (pinfunction "VDD_5") (pintype "unspecified"))
      (node (ref "U3") (pin "1") (pinfunction "A_1") (pintype "unspecified"))
      (node (ref "U3") (pin "5") (pinfunction "VDD_5") (pintype "unspecified"))
      (node (ref "U30") (pin "1") (pinfunction "A_1") (pintype "unspecified"))
      (node (ref "U30") (pin "5") (pinfunction "VDD_5") (pintype "unspecified"))
      (node (ref "U31") (pin "1") (pinfunction "A_1") (pintype "unspecified"))
      (node (ref "U31") (pin "5") (pinfunction "VDD_5") (pintype "unspecified"))
      (node (ref "U32") (pin "1") (pinfunction "A_1") (pintype "unspecified"))
      (node (ref "U32") (pin "5") (pinfunction "VDD_5") (pintype "unspecified"))
      (node (ref "U33") (pin "1") (pinfunction "A_1") (pintype "unspecified"))
      (node (ref "U33") (pin "5") (pinfunction "VDD_5") (pintype "unspecified"))
      (node (ref "U34") (pin "1") (pinfunction "A_1") (pintype "unspecified"))
      (node (ref "U34") (pin "5") (pinfunction "VDD_5") (pintype "unspecified"))
      (node (ref "U35") (pin "1") (pinfunction "A_1") (pintype "unspecified"))
      (node (ref "U35") (pin "5") (pinfunction "VDD_5") (pintype "unspecified"))
      (node (ref "U36") (pin "1") (pinfunction "A_1") (pintype "unspecified"))
      (node (ref "U36") (pin "5") (pinfunction "VDD_5") (pintype "unspecified"))
      (node (ref "U37") (pin "1") (pinfunction "A_1") (pintype "unspecified"))
      (node (ref "U37") (pin "5") (pinfunction "VDD_5") (pintype "unspecified"))
      (node (ref "U38") (pin "1") (pinfunction "A_1") (pintype "unspecified"))
      (node (ref "U38") (pin "5") (pinfunction "VDD_5") (pintype "unspecified"))
      (node (ref "U39") (pin "1") (pinfunction "A_1") (pintype "unspecified"))
      (node (ref "U39") (pin "5") (pinfunction "VDD_5") (pintype "unspecified"))
      (node (ref "U4") (pin "1") (pinfunction "A_1") (pintype "unspecified"))
      (node (ref "U4") (pin "5") (pinfunction "VDD_5") (pintype "unspecified"))
      (node (ref "U40") (pin "1") (pinfunction "A_1") (pintype "unspecified"))
      (node (ref "U40") (pin "5") (pinfunction "VDD_5") (pintype "unspecified"))
      (node (ref "U41") (pin "1") (pinfunction "A_1") (pintype "unspecified"))
      (node (ref "U41") (pin "5") (pinfunction "VDD_5") (pintype "unspecified"))
      (node (ref "U42") (pin "10") (pinfunction "GND_10") (pintype "unspecified"))
      (node (ref "U42") (pin "15") (pinfunction "A0_15") (pintype "unspecified"))
      (node (ref "U43") (pin "1") (pinfunction "A_1") (pintype "unspecified"))
      (node (ref "U43") (pin "5") (pinfunction "VDD_5") (pintype "unspecified"))
      (node (ref "U44") (pin "1") (pinfunction "A_1") (pintype "unspecified"))
      (node (ref "U44") (pin "5") (pinfunction "VDD_5") (pintype "unspecified"))
      (node (ref "U45") (pin "1") (pinfunction "A_1") (pintype "unspecified"))
      (node (ref "U45") (pin "5") (pinfunction "VDD_5") (pintype "unspecified"))
      (node (ref "U46") (pin "1") (pinfunction "A_1") (pintype "unspecified"))
      (node (ref "U46") (pin "5") (pinfunction "VDD_5") (pintype "unspecified"))
      (node (ref "U47") (pin "1") (pinfunction "A_1") (pintype "unspecified"))
      (node (ref "U47") (pin "5") (pinfunction "VDD_5") (pintype "unspecified"))
      (node (ref "U48") (pin "1") (pinfunction "A_1") (pintype "unspecified"))
      (node (ref "U48") (pin "5") (pinfunction "VDD_5") (pintype "unspecified"))
      (node (ref "U49") (pin "1") (pinfunction "A_1") (pintype "unspecified"))
      (node (ref "U49") (pin "5") (pinfunction "VDD_5") (pintype "unspecified"))
      (node (ref "U5") (pin "1") (pinfunction "A_1") (pintype "unspecified"))
      (node (ref "U5") (pin "5") (pinfunction "VDD_5") (pintype "unspecified"))
      (node (ref "U6") (pin "1") (pinfunction "A_1") (pintype "unspecified"))
      (node (ref "U6") (pin "5") (pinfunction "VDD_5") (pintype "unspecified"))
      (node (ref "U7") (pin "1") (pinfunction "A_1") (pintype "unspecified"))
      (node (ref "U7") (pin "5") (pinfunction "VDD_5") (pintype "unspecified"))
      (node (ref "U8") (pin "1") (pinfunction "A_1") (pintype "unspecified"))
      (node (ref "U8") (pin "5") (pinfunction "VDD_5") (pintype "unspecified"))
      (node (ref "U81") (pin "10") (pinfunction "GND_10") (pintype "unspecified"))
      (node (ref "U81") (pin "15") (pinfunction "A0_15") (pintype "unspecified"))
      (node (ref "U81") (pin "16") (pinfunction "A1_16") (pintype "unspecified"))
      (node (ref "U82") (pin "10") (pinfunction "GND_10") (pintype "unspecified"))
      (node (ref "U82") (pin "15") (pinfunction "A0_15") (pintype "unspecified"))
      (node (ref "U82") (pin "17") (pinfunction "A2_17") (pintype "unspecified"))
      (node (ref "U9") (pin "1") (pinfunction "A_1") (pintype "unspecified"))
      (node (ref "U9") (pin "5") (pinfunction "VDD_5") (pintype "unspecified"))
    )
    (net (code "50") (name "LED") (class "Default")
      (node (ref "IC1") (pin "5") (pinfunction "GP3_5") (pintype "unspecified"))
      (node (ref "U22") (pin "A6") (pinfunction "DP1_A6") (pintype "unspecified"))
      (node (ref "U22") (pin "A9") (pinfunction "VBUS_A9") (pintype "unspecified"))
      (node (ref "U22") (pin "B6") (pinfunction "DP2_B6") (pintype "unspecified"))
      (node (ref "U22") (pin "B9") (pinfunction "VBUS_B9") (pintype "unspecified"))
    )
    (net (code "51") (name "LEDOUT") (class "Default")
      (node (ref "IC1") (pin "9") (pinfunction "GP6_9") (pintype "unspecified"))
      (node (ref "U49") (pin "6") (pinfunction "DIN_6") (pintype "unspecified"))
    )
    (net (code "52") (name "Net-(U1-DIN)") (class "Default")
      (node (ref "U1") (pin "6") (pinfunction "DIN_6") (pintype "unspecified"))
      (node (ref "U2") (pin "4") (pinfunction "DO_4") (pintype "unspecified"))
    )
    (net (code "53") (name "Net-(U2-DIN)") (class "Default")
      (node (ref "U2") (pin "6") (pinfunction "DIN_6") (pintype "unspecified"))
      (node (ref "U3") (pin "4") (pinfunction "DO_4") (pintype "unspecified"))
    )
    (net (code "54") (name "Net-(U3-DIN)") (class "Default")
      (node (ref "U3") (pin "6") (pinfunction "DIN_6") (pintype "unspecified"))
      (node (ref "U4") (pin "4") (pinfunction "DO_4") (pintype "unspecified"))
    )
    (net (code "55") (name "Net-(U4-DIN)") (class "Default")
      (node (ref "U4") (pin "6") (pinfunction "DIN_6") (pintype "unspecified"))
      (node (ref "U5") (pin "4") (pinfunction "DO_4") (pintype "unspecified"))
    )
    (net (code "56") (name "Net-(U5-DIN)") (class "Default")
      (node (ref "U5") (pin "6") (pinfunction "DIN_6") (pintype "unspecified"))
      (node (ref "U6") (pin "4") (pinfunction "DO_4") (pintype "unspecified"))
    )
    (net (code "57") (name "Net-(U6-DIN)") (class "Default")
      (node (ref "U6") (pin "6") (pinfunction "DIN_6") (pintype "unspecified"))
      (node (ref "U7") (pin "4") (pinfunction "DO_4") (pintype "unspecified"))
    )
    (net (code "58") (name "Net-(U7-DIN)") (class "Default")
      (node (ref "U7") (pin "6") (pinfunction "DIN_6") (pintype "unspecified"))
      (node (ref "U8") (pin "4") (pinfunction "DO_4") (pintype "unspecified"))
    )
    (net (code "59") (name "Net-(U8-DIN)") (class "Default")
      (node (ref "U8") (pin "6") (pinfunction "DIN_6") (pintype "unspecified"))
      (node (ref "U9") (pin "4") (pinfunction "DO_4") (pintype "unspecified"))
    )
    (net (code "60") (name "Net-(U10-DIN)") (class "Default")
      (node (ref "U10") (pin "6") (pinfunction "DIN_6") (pintype "unspecified"))
      (node (ref "U11") (pin "4") (pinfunction "DO_4") (pintype "unspecified"))
    )
    (net (code "61") (name "Net-(U10-DO)") (class "Default")
      (node (ref "U10") (pin "4") (pinfunction "DO_4") (pintype "unspecified"))
      (node (ref "U9") (pin "6") (pinfunction "DIN_6") (pintype "unspecified"))
    )
    (net (code "62") (name "Net-(U11-DIN)") (class "Default")
      (node (ref "U11") (pin "6") (pinfunction "DIN_6") (pintype "unspecified"))
      (node (ref "U12") (pin "4") (pinfunction "DO_4") (pintype "unspecified"))
    )
    (net (code "63") (name "Net-(U12-DIN)") (class "Default")
      (node (ref "U12") (pin "6") (pinfunction "DIN_6") (pintype "unspecified"))
      (node (ref "U13") (pin "4") (pinfunction "DO_4") (pintype "unspecified"))
    )
    (net (code "64") (name "Net-(U13-DIN)") (class "Default")
      (node (ref "U13") (pin "6") (pinfunction "DIN_6") (pintype "unspecified"))
      (node (ref "U14") (pin "4") (pinfunction "DO_4") (pintype "unspecified"))
    )
    (net (code "65") (name "Net-(U14-DIN)") (class "Default")
      (node (ref "U14") (pin "6") (pinfunction "DIN_6") (pintype "unspecified"))
      (node (ref "U15") (pin "4") (pinfunction "DO_4") (pintype "unspecified"))
    )
    (net (code "66") (name "Net-(U15-DIN)") (class "Default")
      (node (ref "U15") (pin "6") (pinfunction "DIN_6") (pintype "unspecified"))
      (node (ref "U16") (pin "4") (pinfunction "DO_4") (pintype "unspecified"))
    )
    (net (code "67") (name "Net-(U16-DIN)") (class "Default")
      (node (ref "U16") (pin "6") (pinfunction "DIN_6") (pintype "unspecified"))
      (node (ref "U17") (pin "4") (pinfunction "DO_4") (pintype "unspecified"))
    )
    (net (code "68") (name "Net-(U17-DIN)") (class "Default")
      (node (ref "U17") (pin "6") (pinfunction "DIN_6") (pintype "unspecified"))
      (node (ref "U18") (pin "4") (pinfunction "DO_4") (pintype "unspecified"))
    )
    (net (code "69") (name "Net-(U18-DIN)") (class "Default")
      (node (ref "U18") (pin "6") (pinfunction "DIN_6") (pintype "unspecified"))
      (node (ref "U19") (pin "4") (pinfunction "DO_4") (pintype "unspecified"))
    )
    (net (code "70") (name "Net-(U19-DIN)") (class "Default")
      (node (ref "U19") (pin "6") (pinfunction "DIN_6") (pintype "unspecified"))
      (node (ref "U20") (pin "4") (pinfunction "DO_4") (pintype "unspecified"))
    )
    (net (code "71") (name "Net-(U20-DIN)") (class "Default")
      (node (ref "U20") (pin "6") (pinfunction "DIN_6") (pintype "unspecified"))
      (node (ref "U21") (pin "4") (pinfunction "DO_4") (pintype "unspecified"))
    )
    (net (code "72") (name "Net-(U21-DIN)") (class "Default")
      (node (ref "U21") (pin "6") (pinfunction "DIN_6") (pintype "unspecified"))
      (node (ref "U23") (pin "4") (pinfunction "DO_4") (pintype "unspecified"))
    )
    (net (code "73") (name "Net-(U23-DIN)") (class "Default")
      (node (ref "U23") (pin "6") (pinfunction "DIN_6") (pintype "unspecified"))
      (node (ref "U24") (pin "4") (pinfunction "DO_4") (pintype "unspecified"))
    )
    (net (code "74") (name "Net-(U24-DIN)") (class "Default")
      (node (ref "U24") (pin "6") (pinfunction "DIN_6") (pintype "unspecified"))
      (node (ref "U25") (pin "4") (pinfunction "DO_4") (pintype "unspecified"))
    )
    (net (code "75") (name "Net-(U25-DIN)") (class "Default")
      (node (ref "U25") (pin "6") (pinfunction "DIN_6") (pintype "unspecified"))
      (node (ref "U26") (pin "4") (pinfunction "DO_4") (pintype "unspecified"))
    )
    (net (code "76") (name "Net-(U26-DIN)") (class "Default")
      (node (ref "U26") (pin "6") (pinfunction "DIN_6") (pintype "unspecified"))
      (node (ref "U27") (pin "4") (pinfunction "DO_4") (pintype "unspecified"))
    )
    (net (code "77") (name "Net-(U27-DIN)") (class "Default")
      (node (ref "U27") (pin "6") (pinfunction "DIN_6") (pintype "unspecified"))
      (node (ref "U28") (pin "4") (pinfunction "DO_4") (pintype "unspecified"))
    )
    (net (code "78") (name "Net-(U28-DIN)") (class "Default")
      (node (ref "U28") (pin "6") (pinfunction "DIN_6") (pintype "unspecified"))
      (node (ref "U29") (pin "4") (pinfunction "DO_4") (pintype "unspecified"))
    )
    (net (code "79") (name "Net-(U29-DIN)") (class "Default")
      (node (ref "U29") (pin "6") (pinfunction "DIN_6") (pintype "unspecified"))
      (node (ref "U30") (pin "4") (pinfunction "DO_4") (pintype "unspecified"))
    )
    (net (code "80") (name "Net-(U30-DIN)") (class "Default")
      (node (ref "U30") (pin "6") (pinfunction "DIN_6") (pintype "unspecified"))
      (node (ref "U31") (pin "4") (pinfunction "DO_4") (pintype "unspecified"))
    )
    (net (code "81") (name "Net-(U31-DIN)") (class "Default")
      (node (ref "U31") (pin "6") (pinfunction "DIN_6") (pintype "unspecified"))
      (node (ref "U41") (pin "4") (pinfunction "DO_4") (pintype "unspecified"))
    )
    (net (code "82") (name "Net-(U32-DIN)") (class "Default")
      (node (ref "U32") (pin "6") (pinfunction "DIN_6") (pintype "unspecified"))
      (node (ref "U43") (pin "4") (pinfunction "DO_4") (pintype "unspecified"))
    )
    (net (code "83") (name "Net-(U32-DO)") (class "Default")
      (node (ref "U32") (pin "4") (pinfunction "DO_4") (pintype "unspecified"))
      (node (ref "U33") (pin "6") (pinfunction "DIN_6") (pintype "unspecified"))
    )
    (net (code "84") (name "Net-(U33-DO)") (class "Default")
      (node (ref "U33") (pin "4") (pinfunction "DO_4") (pintype "unspecified"))
      (node (ref "U34") (pin "6") (pinfunction "DIN_6") (pintype "unspecified"))
    )
    (net (code "85") (name "Net-(U34-DO)") (class "Default")
      (node (ref "U34") (pin "4") (pinfunction "DO_4") (pintype "unspecified"))
      (node (ref "U35") (pin "6") (pinfunction "DIN_6") (pintype "unspecified"))
    )
    (net (code "86") (name "Net-(U35-DO)") (class "Default")
      (node (ref "U35") (pin "4") (pinfunction "DO_4") (pintype "unspecified"))
      (node (ref "U36") (pin "6") (pinfunction "DIN_6") (pintype "unspecified"))
    )
    (net (code "87") (name "Net-(U36-DO)") (class "Default")
      (node (ref "U36") (pin "4") (pinfunction "DO_4") (pintype "unspecified"))
      (node (ref "U37") (pin "6") (pinfunction "DIN_6") (pintype "unspecified"))
    )
    (net (code "88") (name "Net-(U37-DO)") (class "Default")
      (node (ref "U37") (pin "4") (pinfunction "DO_4") (pintype "unspecified"))
      (node (ref "U38") (pin "6") (pinfunction "DIN_6") (pintype "unspecified"))
    )
    (net (code "89") (name "Net-(U38-DO)") (class "Default")
      (node (ref "U38") (pin "4") (pinfunction "DO_4") (pintype "unspecified"))
      (node (ref "U39") (pin "6") (pinfunction "DIN_6") (pintype "unspecified"))
    )
    (net (code "90") (name "Net-(U39-DO)") (class "Default")
      (node (ref "U39") (pin "4") (pinfunction "DO_4") (pintype "unspecified"))
      (node (ref "U40") (pin "6") (pinfunction "DIN_6") (pintype "unspecified"))
    )
    (net (code "91") (name "Net-(U40-DO)") (class "Default")
      (node (ref "U40") (pin "4") (pinfunction "DO_4") (pintype "unspecified"))
      (node (ref "U41") (pin "6") (pinfunction "DIN_6") (pintype "unspecified"))
    )
    (net (code "92") (name "Net-(U43-DIN)") (class "Default")
      (node (ref "U43") (pin "6") (pinfunction "DIN_6") (pintype "unspecified"))
      (node (ref "U44") (pin "4") (pinfunction "DO_4") (pintype "unspecified"))
    )
    (net (code "93") (name "Net-(U44-DIN)") (class "Default")
      (node (ref "U44") (pin "6") (pinfunction "DIN_6") (pintype "unspecified"))
      (node (ref "U45") (pin "4") (pinfunction "DO_4") (pintype "unspecified"))
    )
    (net (code "94") (name "Net-(U45-DIN)") (class "Default")
      (node (ref "U45") (pin "6") (pinfunction "DIN_6") (pintype "unspecified"))
      (node (ref "U46") (pin "4") (pinfunction "DO_4") (pintype "unspecified"))
    )
    (net (code "95") (name "Net-(U46-DIN)") (class "Default")
      (node (ref "U46") (pin "6") (pinfunction "DIN_6") (pintype "unspecified"))
      (node (ref "U47") (pin "4") (pinfunction "DO_4") (pintype "unspecified"))
    )
    (net (code "96") (name "Net-(U47-DIN)") (class "Default")
      (node (ref "U47") (pin "6") (pinfunction "DIN_6") (pintype "unspecified"))
      (node (ref "U48") (pin "4") (pinfunction "DO_4") (pintype "unspecified"))
    )
    (net (code "97") (name "Net-(U48-DIN)") (class "Default")
      (node (ref "U48") (pin "6") (pinfunction "DIN_6") (pintype "unspecified"))
      (node (ref "U49") (pin "4") (pinfunction "DO_4") (pintype "unspecified"))
    )
    (net (code "98") (name "RX") (class "Default")
      (node (ref "AUDIO1") (pin "3") (pinfunction "3_3") (pintype "unspecified"))
      (node (ref "IC1") (pin "11") (pinfunction "GP8_11") (pintype "unspecified"))
    )
    (net (code "99") (name "SCL") (class "Default")
      (node (ref "IC1") (pin "7") (pinfunction "GP5_7") (pintype "unspecified"))
      (node (ref "R2") (pin "1") (pinfunction "1_1") (pintype "unspecified"))
      (node (ref "U22") (pin "A10") (pinfunction "SSRXn2_A10") (pintype "unspecified"))
      (node (ref "U22") (pin "B10") (pinfunction "SSRXn1_B10") (pintype "unspecified"))
      (node (ref "U42") (pin "12") (pinfunction "SCL_12") (pintype "unspecified"))
      (node (ref "U81") (pin "12") (pinfunction "SCL_12") (pintype "unspecified"))
      (node (ref "U82") (pin "12") (pinfunction "SCL_12") (pintype "unspecified"))
    )
    (net (code "100") (name "SDA") (class "Default")
      (node (ref "IC1") (pin "6") (pinfunction "GP4_6") (pintype "unspecified"))
      (node (ref "R1") (pin "1") (pinfunction "1_1") (pintype "unspecified"))
      (node (ref "U22") (pin "A11") (pinfunction "SSRXp2_A11") (pintype "unspecified"))
      (node (ref "U22") (pin "B11") (pinfunction "SSRXp1_B11") (pintype "unspecified"))
      (node (ref "U42") (pin "13") (pinfunction "SDA_13") (pintype "unspecified"))
      (node (ref "U81") (pin "13") (pinfunction "SDA_13") (pintype "unspecified"))
      (node (ref "U82") (pin "13") (pinfunction "SDA_13") (pintype "unspecified"))
    )
    (net (code "101") (name "TX") (class "Default")
      (node (ref "AUDIO1") (pin "2") (pinfunction "2_2") (pintype "unspecified"))
      (node (ref "IC1") (pin "12") (pinfunction "GP9_12") (pintype "unspecified"))
    )
    (net (code "102") (name "VCC") (class "Default")
      (node (ref "AUDIO1") (pin "4") (pinfunction "4_4") (pintype "unspecified"))
      (node (ref "IC1") (pin "39") (pinfunction "Vin_39") (pintype "unspecified"))
      (node (ref "U22") (pin "A7") (pinfunction "DN1_A7") (pintype "unspecified"))
      (node (ref "U22") (pin "B7") (pinfunction "DN2_B7") (pintype "unspecified"))
      (node (ref "U42") (pin "16") (pinfunction "A1_16") (pintype "unspecified"))
      (node (ref "U42") (pin "17") (pinfunction "A2_17") (pintype "unspecified"))
      (node (ref "U42") (pin "9") (pinfunction "Vdd_9") (pintype "unspecified"))
      (node (ref "U81") (pin "17") (pinfunction "A2_17") (pintype "unspecified"))
      (node (ref "U81") (pin "9") (pinfunction "Vdd_9") (pintype "unspecified"))
      (node (ref "U82") (pin "16") (pinfunction "A1_16") (pintype "unspecified"))
      (node (ref "U82") (pin "9") (pinfunction "Vdd_9") (pintype "unspecified"))
    )
    (net (code "103") (name "unconnected-(IC1-3V3-Pad41)") (class "Default")
      (node (ref "IC1") (pin "41") (pinfunction "3V3_41") (pintype "unspecified+no_connect"))
    )
    (net (code "104") (name "unconnected-(IC1-GND-Pad44)") (class "Default")
      (node (ref "IC1") (pin "44") (pinfunction "GND_44") (pintype "unspecified+no_connect"))
    )
    (net (code "105") (name "unconnected-(IC1-GP0-Pad1)") (class "Default")
      (node (ref "IC1") (pin "1") (pinfunction "GP0_1") (pintype "unspecified+no_connect"))
    )
    (net (code "106") (name "unconnected-(IC1-GP1-Pad2)") (class "Default")
      (node (ref "IC1") (pin "2") (pinfunction "GP1_2") (pintype "unspecified+no_connect"))
    )
    (net (code "107") (name "unconnected-(IC1-GP2-Pad4)") (class "Default")
      (node (ref "IC1") (pin "4") (pinfunction "GP2_4") (pintype "unspecified+no_connect"))
    )
    (net (code "108") (name "unconnected-(IC1-GP7-Pad10)") (class "Default")
      (node (ref "IC1") (pin "10") (pinfunction "GP7_10") (pintype "unspecified+no_connect"))
    )
    (net (code "109") (name "unconnected-(IC1-GP10-Pad14)") (class "Default")
      (node (ref "IC1") (pin "14") (pinfunction "GP10_14") (pintype "unspecified+no_connect"))
    )
    (net (code "110") (name "unconnected-(IC1-GP11-Pad15)") (class "Default")
      (node (ref "IC1") (pin "15") (pinfunction "GP11_15") (pintype "unspecified+no_connect"))
    )
    (net (code "111") (name "unconnected-(IC1-GP12-Pad16)") (class "Default")
      (node (ref "IC1") (pin "16") (pinfunction "GP12_16") (pintype "unspecified+no_connect"))
    )
    (net (code "112") (name "unconnected-(IC1-GP13-Pad17)") (class "Default")
      (node (ref "IC1") (pin "17") (pinfunction "GP13_17") (pintype "unspecified+no_connect"))
    )
    (net (code "113") (name "unconnected-(IC1-GP14-Pad19)") (class "Default")
      (node (ref "IC1") (pin "19") (pinfunction "GP14_19") (pintype "unspecified+no_connect"))
    )
    (net (code "114") (name "unconnected-(IC1-GP15-Pad20)") (class "Default")
      (node (ref "IC1") (pin "20") (pinfunction "GP15_20") (pintype "unspecified+no_connect"))
    )
    (net (code "115") (name "unconnected-(IC1-GP16-Pad21)") (class "Default")
      (node (ref "IC1") (pin "21") (pinfunction "GP16_21") (pintype "unspecified+no_connect"))
    )
    (net (code "116") (name "unconnected-(IC1-GP17-Pad22)") (class "Default")
      (node (ref "IC1") (pin "22") (pinfunction "GP17_22") (pintype "unspecified+no_connect"))
    )
    (net (code "117") (name "unconnected-(IC1-GP18-Pad24)") (class "Default")
      (node (ref "IC1") (pin "24") (pinfunction "GP18_24") (pintype "unspecified+no_connect"))
    )
    (net (code "118") (name "unconnected-(IC1-GP19-Pad25)") (class "Default")
      (node (ref "IC1") (pin "25") (pinfunction "GP19_25") (pintype "unspecified+no_connect"))
    )
    (net (code "119") (name "unconnected-(IC1-GP20-Pad26)") (class "Default")
      (node (ref "IC1") (pin "26") (pinfunction "GP20_26") (pintype "unspecified+no_connect"))
    )
    (net (code "120") (name "unconnected-(IC1-GP21-Pad27)") (class "Default")
      (node (ref "IC1") (pin "27") (pinfunction "GP21_27") (pintype "unspecified+no_connect"))
    )
    (net (code "121") (name "unconnected-(IC1-GP22-Pad29)") (class "Default")
      (node (ref "IC1") (pin "29") (pinfunction "GP22_29") (pintype "unspecified+no_connect"))
    )
    (net (code "122") (name "unconnected-(IC1-GP23-Pad37)") (class "Default")
      (node (ref "IC1") (pin "37") (pinfunction "GP23_37") (pintype "unspecified+no_connect"))
    )
    (net (code "123") (name "unconnected-(IC1-GP26-Pad31)") (class "Default")
      (node (ref "IC1") (pin "31") (pinfunction "GP26_31") (pintype "unspecified+no_connect"))
    )
    (net (code "124") (name "unconnected-(IC1-GP27-Pad32)") (class "Default")
      (node (ref "IC1") (pin "32") (pinfunction "GP27_32") (pintype "unspecified+no_connect"))
    )
    (net (code "125") (name "unconnected-(IC1-GP28-Pad34)") (class "Default")
      (node (ref "IC1") (pin "34") (pinfunction "GP28_34") (pintype "unspecified+no_connect"))
    )
    (net (code "126") (name "unconnected-(IC1-GP29-Pad35)") (class "Default")
      (node (ref "IC1") (pin "35") (pinfunction "GP29_35") (pintype "unspecified+no_connect"))
    )
    (net (code "127") (name "unconnected-(IC1-RUN-Pad30)") (class "Default")
      (node (ref "IC1") (pin "30") (pinfunction "RUN_30") (pintype "unspecified+no_connect"))
    )
    (net (code "128") (name "unconnected-(IC1-SWDCLK-Pad43)") (class "Default")
      (node (ref "IC1") (pin "43") (pinfunction "SWDCLK_43") (pintype "unspecified+no_connect"))
    )
    (net (code "129") (name "unconnected-(IC1-SWDIO-Pad42)") (class "Default")
      (node (ref "IC1") (pin "42") (pinfunction "SWDIO_42") (pintype "unspecified+no_connect"))
    )
    (net (code "130") (name "unconnected-(IC1-Vout-Pad40)") (class "Default")
      (node (ref "IC1") (pin "40") (pinfunction "Vout_40") (pintype "unspecified+no_connect"))
    )
    (net (code "131") (name "unconnected-(U1-DO-Pad4)") (class "Default")
      (node (ref "U1") (pin "4") (pinfunction "DO_4") (pintype "unspecified+no_connect"))
    )
    (net (code "132") (name "unconnected-(U22-SSTXP1-PadA2)") (class "Default")
      (node (ref "U22") (pin "A2") (pinfunction "SSTXP1_A2") (pintype "unspecified+no_connect"))
    )
    (net (code "133") (name "unconnected-(U22-SSTXn1-PadA3)") (class "Default")
      (node (ref "U22") (pin "A3") (pinfunction "SSTXn1_A3") (pintype "unspecified+no_connect"))
    )
    (net (code "134") (name "unconnected-(U22-SSTXn2-PadB3)") (class "Default")
      (node (ref "U22") (pin "B3") (pinfunction "SSTXn2_B3") (pintype "unspecified+no_connect"))
    )
    (net (code "135") (name "unconnected-(U22-SSTXp2-PadB2)") (class "Default")
      (node (ref "U22") (pin "B2") (pinfunction "SSTXp2_B2") (pintype "unspecified+no_connect"))
    )
    (net (code "136") (name "unconnected-(U22-VBUS-PadA4)") (class "Default")
      (node (ref "U22") (pin "A4") (pinfunction "VBUS_A4") (pintype "unspecified+no_connect"))
    )
    (net (code "137") (name "unconnected-(U22-VBUS-PadB4)") (class "Default")
      (node (ref "U22") (pin "B4") (pinfunction "VBUS_B4") (pintype "unspecified+no_connect"))
    )
    (net (code "138") (name "unconnected-(U42-GB7-Pad8)") (class "Default")
      (node (ref "U42") (pin "8") (pinfunction "GB7_8") (pintype "unspecified"))
    )
    (net (code "139") (name "unconnected-(U42-INTa-Pad20)") (class "Default")
      (node (ref "U42") (pin "20") (pinfunction "INTa_20") (pintype "unspecified+no_connect"))
    )
    (net (code "140") (name "unconnected-(U42-INTb-Pad19)") (class "Default")
      (node (ref "U42") (pin "19") (pinfunction "INTb_19") (pintype "unspecified+no_connect"))
    )
    (net (code "141") (name "unconnected-(U42-NC-Pad11)") (class "Default")
      (node (ref "U42") (pin "11") (pinfunction "NC_11") (pintype "unspecified+no_connect"))
    )
    (net (code "142") (name "unconnected-(U42-NC-Pad14)") (class "Default")
      (node (ref "U42") (pin "14") (pinfunction "NC_14") (pintype "unspecified+no_connect"))
    )
    (net (code "143") (name "unconnected-(U42-^RST-Pad18)") (class "Default")
      (node (ref "U42") (pin "18") (pinfunction "^RST_18") (pintype "unspecified+no_connect"))
    )
    (net (code "144") (name "unconnected-(U81-INTa-Pad20)") (class "Default")
      (node (ref "U81") (pin "20") (pinfunction "INTa_20") (pintype "unspecified+no_connect"))
    )
    (net (code "145") (name "unconnected-(U81-INTb-Pad19)") (class "Default")
      (node (ref "U81") (pin "19") (pinfunction "INTb_19") (pintype "unspecified+no_connect"))
    )
    (net (code "146") (name "unconnected-(U81-NC-Pad11)") (class "Default")
      (node (ref "U81") (pin "11") (pinfunction "NC_11") (pintype "unspecified+no_connect"))
    )
    (net (code "147") (name "unconnected-(U81-NC-Pad14)") (class "Default")
      (node (ref "U81") (pin "14") (pinfunction "NC_14") (pintype "unspecified+no_connect"))
    )
    (net (code "148") (name "unconnected-(U81-^RST-Pad18)") (class "Default")
      (node (ref "U81") (pin "18") (pinfunction "^RST_18") (pintype "unspecified+no_connect"))
    )
    (net (code "149") (name "unconnected-(U82-INTa-Pad20)") (class "Default")
      (node (ref "U82") (pin "20") (pinfunction "INTa_20") (pintype "unspecified+no_connect"))
    )
    (net (code "150") (name "unconnected-(U82-INTb-Pad19)") (class "Default")
      (node (ref "U82") (pin "19") (pinfunction "INTb_19") (pintype "unspecified+no_connect"))
    )
    (net (code "151") (name "unconnected-(U82-NC-Pad11)") (class "Default")
      (node (ref "U82") (pin "11") (pinfunction "NC_11") (pintype "unspecified+no_connect"))
    )
    (net (code "152") (name "unconnected-(U82-NC-Pad14)") (class "Default")
      (node (ref "U82") (pin "14") (pinfunction "NC_14") (pintype "unspecified+no_connect"))
    )
    (net (code "153") (name "unconnected-(U82-^RST-Pad18)") (class "Default")
      (node (ref "U82") (pin "18") (pinfunction "^RST_18") (pintype "unspecified+no_connect"))
    )
  )
)
